# RPi-WS2812-HAT_v10.net
KiCad netlist of a schematic drawn in EAGLE
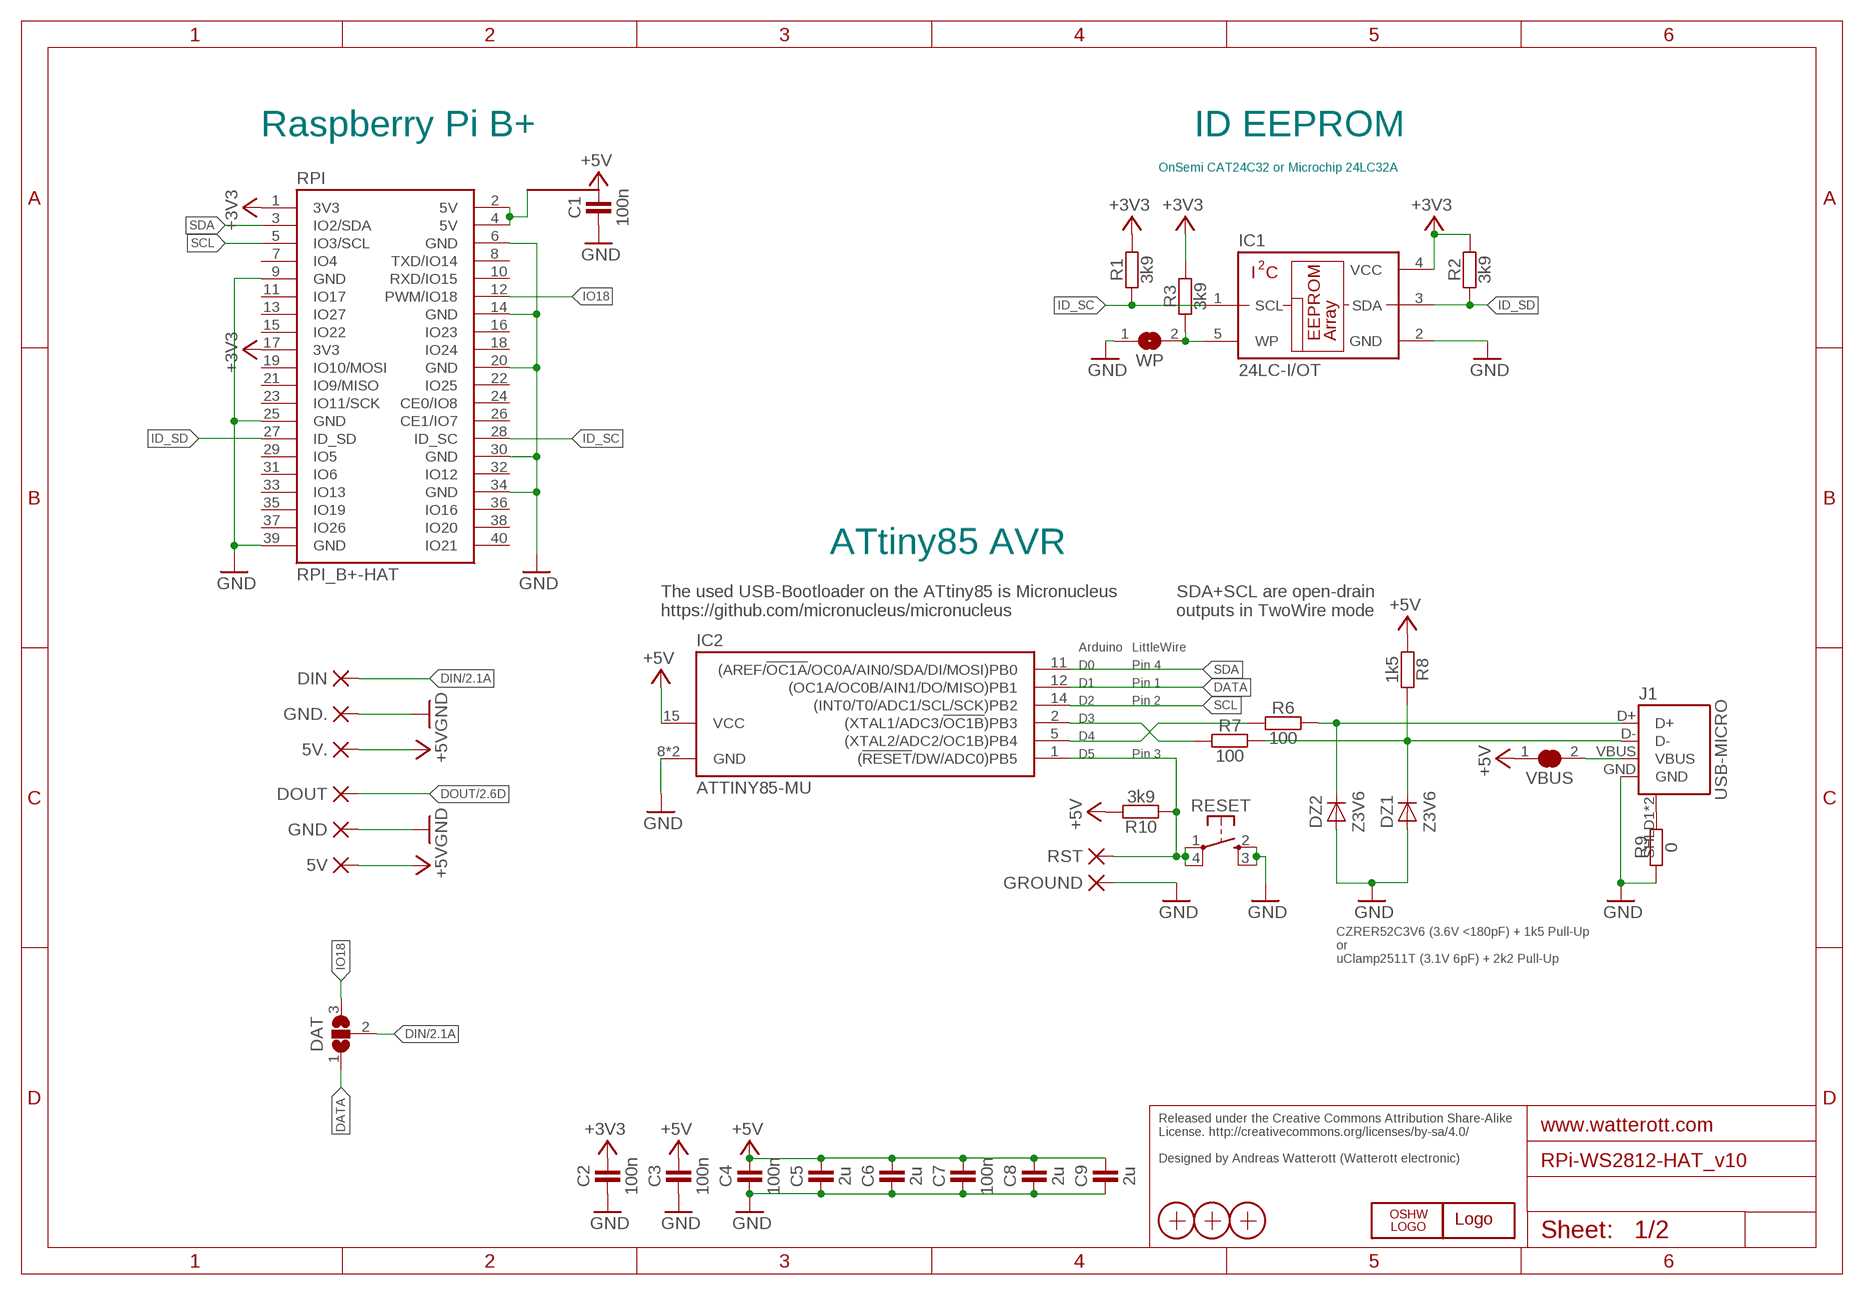
[diagram p0: schematic, sheet 1]
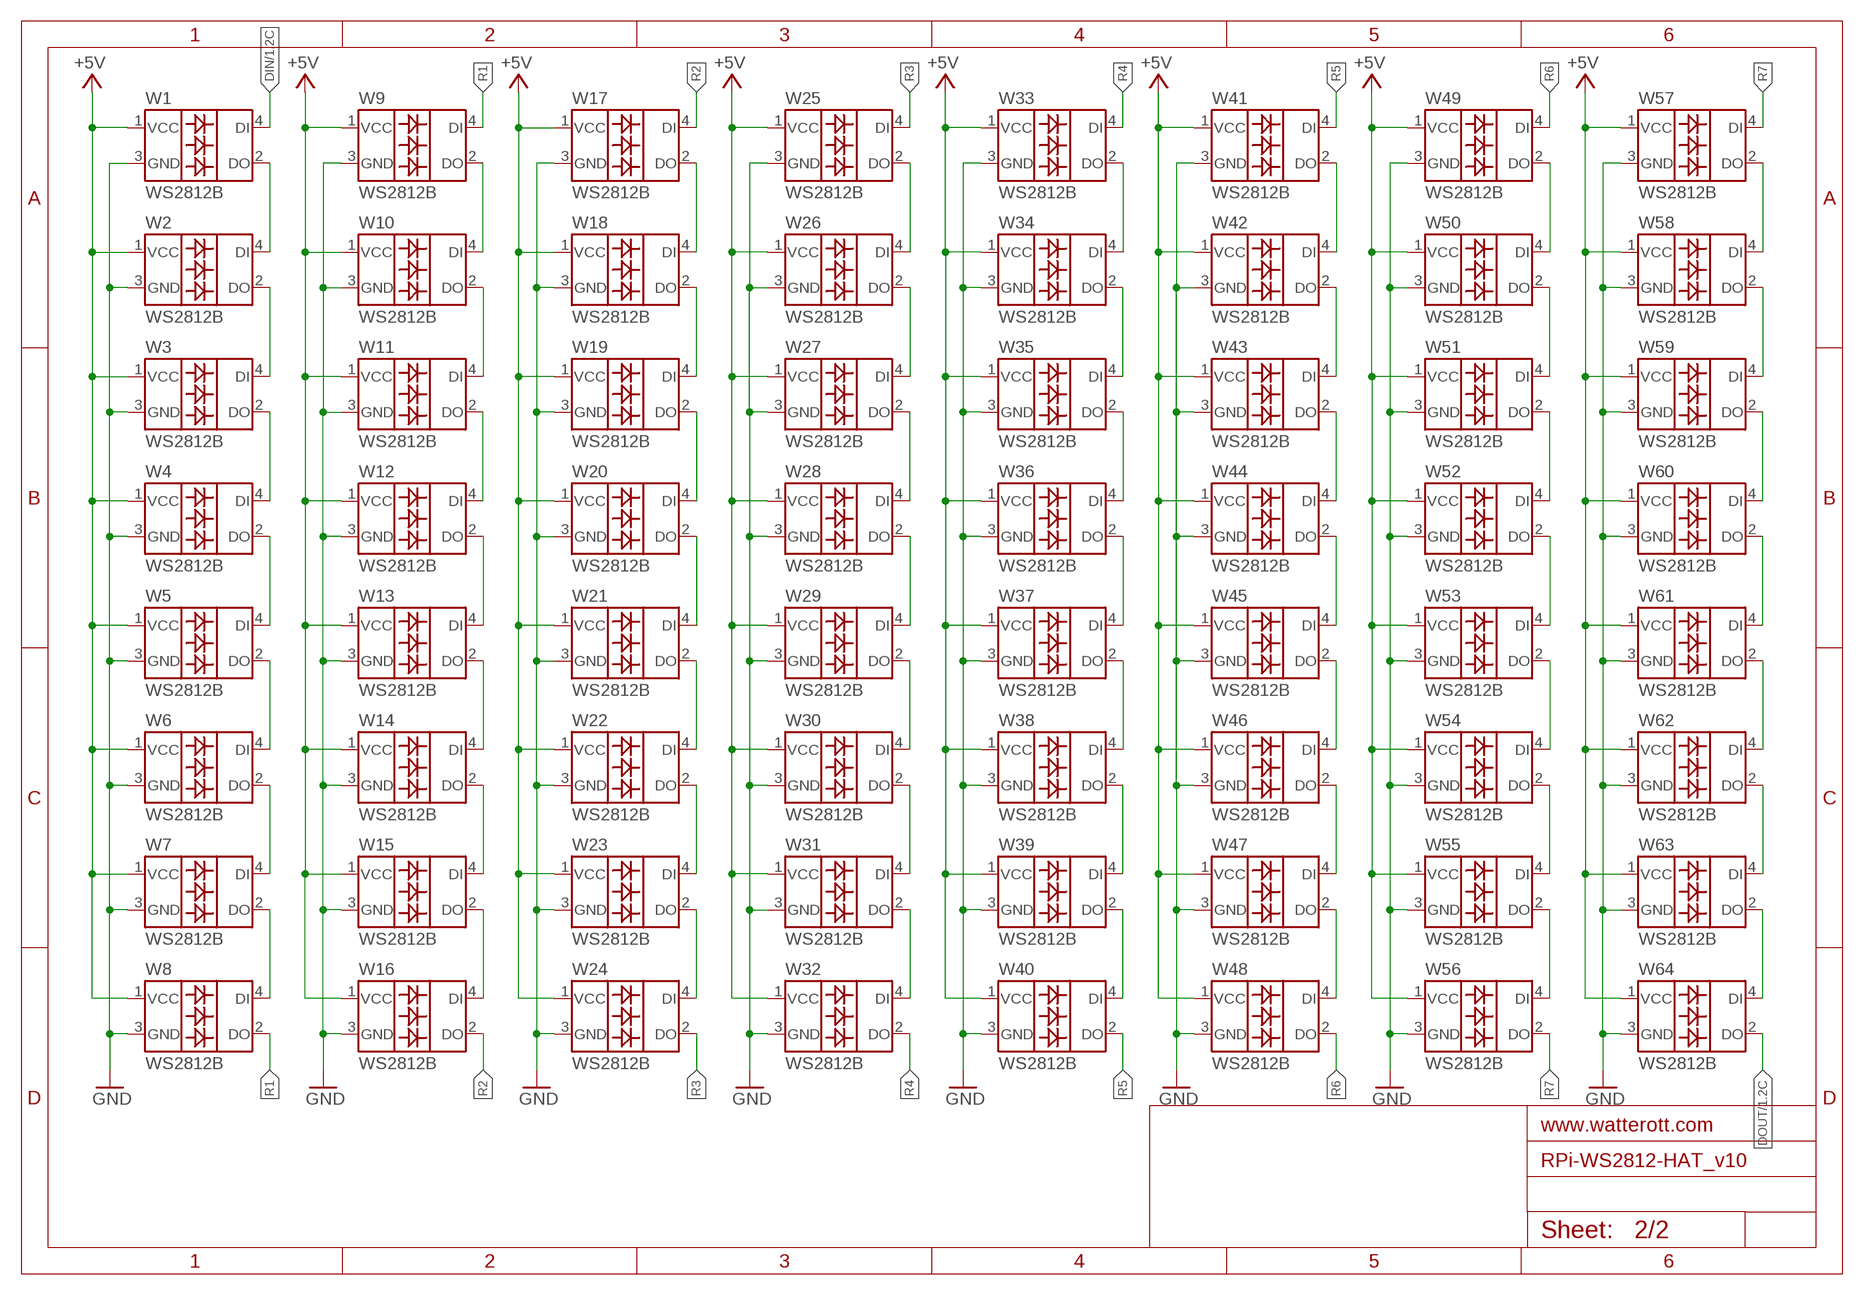
[diagram p1: schematic, sheet 2]

(export (version "E")
  (design (tool "Eeschema 10.0.6"))
  (components
    (comp (ref "5V")
      (value "PAD-1.27X2.54_NC")
      (footprint "eagle-import:PAD-1.27X2.54_NC")
      (libsource (lib "eagle-import") (part "PAD-1.27X2.54_NC"))
    )
    (comp (ref "5V.")
      (value "PAD-1.27X2.54_NC")
      (footprint "eagle-import:PAD-1.27X2.54_NC")
      (libsource (lib "eagle-import") (part "PAD-1.27X2.54_NC"))
    )
    (comp (ref "C1")
      (value "100n")
      (footprint "eagle-import:C0402")
      (libsource (lib "eagle-import") (part "CAPACITOR-0402"))
    )
    (comp (ref "C2")
      (value "100n")
      (footprint "eagle-import:C0402")
      (libsource (lib "eagle-import") (part "CAPACITOR-0402"))
    )
    (comp (ref "C3")
      (value "100n")
      (footprint "eagle-import:C0402")
      (libsource (lib "eagle-import") (part "CAPACITOR-0402"))
    )
    (comp (ref "C4")
      (value "100n")
      (footprint "eagle-import:C0402")
      (libsource (lib "eagle-import") (part "CAPACITOR-0402"))
    )
    (comp (ref "C5")
      (value "2u")
      (footprint "eagle-import:C0402")
      (libsource (lib "eagle-import") (part "CAPACITOR-0402"))
    )
    (comp (ref "C6")
      (value "2u")
      (footprint "eagle-import:C0402")
      (libsource (lib "eagle-import") (part "CAPACITOR-0402"))
    )
    (comp (ref "C7")
      (value "100n")
      (footprint "eagle-import:C0402")
      (libsource (lib "eagle-import") (part "CAPACITOR-0402"))
    )
    (comp (ref "C8")
      (value "2u")
      (footprint "eagle-import:C0402")
      (libsource (lib "eagle-import") (part "CAPACITOR-0402"))
    )
    (comp (ref "C9")
      (value "2u")
      (footprint "eagle-import:C0402")
      (libsource (lib "eagle-import") (part "CAPACITOR-0402"))
    )
    (comp (ref "DAT")
      (value "JUMPER3-0603")
      (footprint "eagle-import:JUMPER3-0603")
      (libsource (lib "eagle-import") (part "JUMPER3-0603"))
    )
    (comp (ref "DIN")
      (value "PAD-1.27X2.54_NC")
      (footprint "eagle-import:PAD-1.27X2.54_NC")
      (libsource (lib "eagle-import") (part "PAD-1.27X2.54_NC"))
    )
    (comp (ref "DOUT")
      (value "PAD-1.27X2.54_NC")
      (footprint "eagle-import:PAD-1.27X2.54_NC")
      (libsource (lib "eagle-import") (part "PAD-1.27X2.54_NC"))
    )
    (comp (ref "DZ1")
      (value "Z3V6")
      (footprint "eagle-import:SOD882")
      (libsource (lib "eagle-import") (part "DIODE-SOD882"))
    )
    (comp (ref "DZ2")
      (value "Z3V6")
      (footprint "eagle-import:SOD882")
      (libsource (lib "eagle-import") (part "DIODE-SOD882"))
    )
    (comp (ref "GND")
      (value "PAD-1.27X2.54_NC")
      (footprint "eagle-import:PAD-1.27X2.54_NC")
      (libsource (lib "eagle-import") (part "PAD-1.27X2.54_NC"))
    )
    (comp (ref "GND.")
      (value "PAD-1.27X2.54_NC")
      (footprint "eagle-import:PAD-1.27X2.54_NC")
      (libsource (lib "eagle-import") (part "PAD-1.27X2.54_NC"))
    )
    (comp (ref "GROUND")
      (value "PAD-1.27X1.27_NC")
      (footprint "eagle-import:PAD-1.27X1.27_NC")
      (libsource (lib "eagle-import") (part "PAD-1.27X1.27_NC"))
    )
    (comp (ref "IC1")
      (value "24LC-I/OT")
      (footprint "eagle-import:SOT23-5")
      (libsource (lib "eagle-import") (part "24LC-I/OT"))
    )
    (comp (ref "IC2")
      (value "ATTINY85-MU")
      (footprint "eagle-import:QFN20-PAD")
      (libsource (lib "eagle-import") (part "ATTINY85-MU"))
    )
    (comp (ref "J1")
      (value "USB-MICRO")
      (footprint "eagle-import:USB-MICRO-10103594")
      (libsource (lib "eagle-import") (part "USB-MICRO"))
    )
    (comp (ref "LOGO1")
      (value "LOGO-S_PLACE_S")
      (footprint "eagle-import:SPARK_TPLACE_S")
      (libsource (lib "eagle-import") (part "LOGO-S_PLACE_S"))
    )
    (comp (ref "LOGO2")
      (value "OSHW_LOGOX0070")
      (footprint "eagle-import:OSHW_6X70")
      (libsource (lib "eagle-import") (part "OSHW_LOGOX0070"))
    )
    (comp (ref "R1")
      (value "3k9")
      (footprint "eagle-import:C0402")
      (libsource (lib "eagle-import") (part "RESISTOR-0402"))
    )
    (comp (ref "R2")
      (value "3k9")
      (footprint "eagle-import:C0402")
      (libsource (lib "eagle-import") (part "RESISTOR-0402"))
    )
    (comp (ref "R3")
      (value "3k9")
      (footprint "eagle-import:C0402")
      (libsource (lib "eagle-import") (part "RESISTOR-0402"))
    )
    (comp (ref "R6")
      (value "100")
      (footprint "eagle-import:C0402")
      (libsource (lib "eagle-import") (part "RESISTOR-0402"))
    )
    (comp (ref "R7")
      (value "100")
      (footprint "eagle-import:C0402")
      (libsource (lib "eagle-import") (part "RESISTOR-0402"))
    )
    (comp (ref "R8")
      (value "1k5")
      (footprint "eagle-import:C0402")
      (libsource (lib "eagle-import") (part "RESISTOR-0402"))
    )
    (comp (ref "R9")
      (value "0")
      (footprint "eagle-import:C0402")
      (libsource (lib "eagle-import") (part "RESISTOR-0402"))
    )
    (comp (ref "R10")
      (value "3k9")
      (footprint "eagle-import:C0402")
      (libsource (lib "eagle-import") (part "RESISTOR-0402"))
    )
    (comp (ref "RESET")
      (value "SW-TACTILE-TL3315")
      (footprint "eagle-import:SW_TL3315N")
      (libsource (lib "eagle-import") (part "SW-TACTILE-TL3315"))
    )
    (comp (ref "RPI")
      (value "RPI_B+-HAT")
      (footprint "eagle-import:RPI-B+HAT")
      (libsource (lib "eagle-import") (part "RPI_B+-HAT"))
    )
    (comp (ref "RST")
      (value "PAD-1.27X1.27_NC")
      (footprint "eagle-import:PAD-1.27X1.27_NC")
      (libsource (lib "eagle-import") (part "PAD-1.27X1.27_NC"))
    )
    (comp (ref "VBUS")
      (value "JUMPER2-0603-NC")
      (footprint "eagle-import:JUMPER2-0603_NC")
      (libsource (lib "eagle-import") (part "JUMPER2-0603-NC"))
    )
    (comp (ref "WP")
      (value "JUMPER2-0603-NC")
      (footprint "eagle-import:JUMPER2-0603_NC")
      (libsource (lib "eagle-import") (part "JUMPER2-0603-NC"))
    )
    (comp (ref "X1")
      (value "PASSER-07")
      (footprint "eagle-import:PASSER_07MM")
      (libsource (lib "eagle-import") (part "PASSER-07"))
    )
    (comp (ref "X2")
      (value "PASSER-07")
      (footprint "eagle-import:PASSER_07MM")
      (libsource (lib "eagle-import") (part "PASSER-07"))
    )
    (comp (ref "X3")
      (value "PASSER-07")
      (footprint "eagle-import:PASSER_07MM")
      (libsource (lib "eagle-import") (part "PASSER-07"))
    )
    (comp (ref "W1")
      (value "WS2812B")
      (footprint "eagle-import:WS2812B")
      (libsource (lib "eagle-import") (part "WS2812B"))
    )
    (comp (ref "W2")
      (value "WS2812B")
      (footprint "eagle-import:WS2812B")
      (libsource (lib "eagle-import") (part "WS2812B"))
    )
    (comp (ref "W3")
      (value "WS2812B")
      (footprint "eagle-import:WS2812B")
      (libsource (lib "eagle-import") (part "WS2812B"))
    )
    (comp (ref "W4")
      (value "WS2812B")
      (footprint "eagle-import:WS2812B")
      (libsource (lib "eagle-import") (part "WS2812B"))
    )
    (comp (ref "W5")
      (value "WS2812B")
      (footprint "eagle-import:WS2812B")
      (libsource (lib "eagle-import") (part "WS2812B"))
    )
    (comp (ref "W6")
      (value "WS2812B")
      (footprint "eagle-import:WS2812B")
      (libsource (lib "eagle-import") (part "WS2812B"))
    )
    (comp (ref "W7")
      (value "WS2812B")
      (footprint "eagle-import:WS2812B")
      (libsource (lib "eagle-import") (part "WS2812B"))
    )
    (comp (ref "W8")
      (value "WS2812B")
      (footprint "eagle-import:WS2812B")
      (libsource (lib "eagle-import") (part "WS2812B"))
    )
    (comp (ref "W9")
      (value "WS2812B")
      (footprint "eagle-import:WS2812B")
      (libsource (lib "eagle-import") (part "WS2812B"))
    )
    (comp (ref "W10")
      (value "WS2812B")
      (footprint "eagle-import:WS2812B")
      (libsource (lib "eagle-import") (part "WS2812B"))
    )
    (comp (ref "W11")
      (value "WS2812B")
      (footprint "eagle-import:WS2812B")
      (libsource (lib "eagle-import") (part "WS2812B"))
    )
    (comp (ref "W12")
      (value "WS2812B")
      (footprint "eagle-import:WS2812B")
      (libsource (lib "eagle-import") (part "WS2812B"))
    )
    (comp (ref "W13")
      (value "WS2812B")
      (footprint "eagle-import:WS2812B")
      (libsource (lib "eagle-import") (part "WS2812B"))
    )
    (comp (ref "W14")
      (value "WS2812B")
      (footprint "eagle-import:WS2812B")
      (libsource (lib "eagle-import") (part "WS2812B"))
    )
    (comp (ref "W15")
      (value "WS2812B")
      (footprint "eagle-import:WS2812B")
      (libsource (lib "eagle-import") (part "WS2812B"))
    )
    (comp (ref "W16")
      (value "WS2812B")
      (footprint "eagle-import:WS2812B")
      (libsource (lib "eagle-import") (part "WS2812B"))
    )
    (comp (ref "W17")
      (value "WS2812B")
      (footprint "eagle-import:WS2812B")
      (libsource (lib "eagle-import") (part "WS2812B"))
    )
    (comp (ref "W18")
      (value "WS2812B")
      (footprint "eagle-import:WS2812B")
      (libsource (lib "eagle-import") (part "WS2812B"))
    )
    (comp (ref "W19")
      (value "WS2812B")
      (footprint "eagle-import:WS2812B")
      (libsource (lib "eagle-import") (part "WS2812B"))
    )
    (comp (ref "W20")
      (value "WS2812B")
      (footprint "eagle-import:WS2812B")
      (libsource (lib "eagle-import") (part "WS2812B"))
    )
    (comp (ref "W21")
      (value "WS2812B")
      (footprint "eagle-import:WS2812B")
      (libsource (lib "eagle-import") (part "WS2812B"))
    )
    (comp (ref "W22")
      (value "WS2812B")
      (footprint "eagle-import:WS2812B")
      (libsource (lib "eagle-import") (part "WS2812B"))
    )
    (comp (ref "W23")
      (value "WS2812B")
      (footprint "eagle-import:WS2812B")
      (libsource (lib "eagle-import") (part "WS2812B"))
    )
    (comp (ref "W24")
      (value "WS2812B")
      (footprint "eagle-import:WS2812B")
      (libsource (lib "eagle-import") (part "WS2812B"))
    )
    (comp (ref "W25")
      (value "WS2812B")
      (footprint "eagle-import:WS2812B")
      (libsource (lib "eagle-import") (part "WS2812B"))
    )
    (comp (ref "W26")
      (value "WS2812B")
      (footprint "eagle-import:WS2812B")
      (libsource (lib "eagle-import") (part "WS2812B"))
    )
    (comp (ref "W27")
      (value "WS2812B")
      (footprint "eagle-import:WS2812B")
      (libsource (lib "eagle-import") (part "WS2812B"))
    )
    (comp (ref "W28")
      (value "WS2812B")
      (footprint "eagle-import:WS2812B")
      (libsource (lib "eagle-import") (part "WS2812B"))
    )
    (comp (ref "W29")
      (value "WS2812B")
      (footprint "eagle-import:WS2812B")
      (libsource (lib "eagle-import") (part "WS2812B"))
    )
    (comp (ref "W30")
      (value "WS2812B")
      (footprint "eagle-import:WS2812B")
      (libsource (lib "eagle-import") (part "WS2812B"))
    )
    (comp (ref "W31")
      (value "WS2812B")
      (footprint "eagle-import:WS2812B")
      (libsource (lib "eagle-import") (part "WS2812B"))
    )
    (comp (ref "W32")
      (value "WS2812B")
      (footprint "eagle-import:WS2812B")
      (libsource (lib "eagle-import") (part "WS2812B"))
    )
    (comp (ref "W33")
      (value "WS2812B")
      (footprint "eagle-import:WS2812B")
      (libsource (lib "eagle-import") (part "WS2812B"))
    )
    (comp (ref "W34")
      (value "WS2812B")
      (footprint "eagle-import:WS2812B")
      (libsource (lib "eagle-import") (part "WS2812B"))
    )
    (comp (ref "W35")
      (value "WS2812B")
      (footprint "eagle-import:WS2812B")
      (libsource (lib "eagle-import") (part "WS2812B"))
    )
    (comp (ref "W36")
      (value "WS2812B")
      (footprint "eagle-import:WS2812B")
      (libsource (lib "eagle-import") (part "WS2812B"))
    )
    (comp (ref "W37")
      (value "WS2812B")
      (footprint "eagle-import:WS2812B")
      (libsource (lib "eagle-import") (part "WS2812B"))
    )
    (comp (ref "W38")
      (value "WS2812B")
      (footprint "eagle-import:WS2812B")
      (libsource (lib "eagle-import") (part "WS2812B"))
    )
    (comp (ref "W39")
      (value "WS2812B")
      (footprint "eagle-import:WS2812B")
      (libsource (lib "eagle-import") (part "WS2812B"))
    )
    (comp (ref "W40")
      (value "WS2812B")
      (footprint "eagle-import:WS2812B")
      (libsource (lib "eagle-import") (part "WS2812B"))
    )
    (comp (ref "W41")
      (value "WS2812B")
      (footprint "eagle-import:WS2812B")
      (libsource (lib "eagle-import") (part "WS2812B"))
    )
    (comp (ref "W42")
      (value "WS2812B")
      (footprint "eagle-import:WS2812B")
      (libsource (lib "eagle-import") (part "WS2812B"))
    )
    (comp (ref "W43")
      (value "WS2812B")
      (footprint "eagle-import:WS2812B")
      (libsource (lib "eagle-import") (part "WS2812B"))
    )
    (comp (ref "W44")
      (value "WS2812B")
      (footprint "eagle-import:WS2812B")
      (libsource (lib "eagle-import") (part "WS2812B"))
    )
    (comp (ref "W45")
      (value "WS2812B")
      (footprint "eagle-import:WS2812B")
      (libsource (lib "eagle-import") (part "WS2812B"))
    )
    (comp (ref "W46")
      (value "WS2812B")
      (footprint "eagle-import:WS2812B")
      (libsource (lib "eagle-import") (part "WS2812B"))
    )
    (comp (ref "W47")
      (value "WS2812B")
      (footprint "eagle-import:WS2812B")
      (libsource (lib "eagle-import") (part "WS2812B"))
    )
    (comp (ref "W48")
      (value "WS2812B")
      (footprint "eagle-import:WS2812B")
      (libsource (lib "eagle-import") (part "WS2812B"))
    )
    (comp (ref "W49")
      (value "WS2812B")
      (footprint "eagle-import:WS2812B")
      (libsource (lib "eagle-import") (part "WS2812B"))
    )
    (comp (ref "W50")
      (value "WS2812B")
      (footprint "eagle-import:WS2812B")
      (libsource (lib "eagle-import") (part "WS2812B"))
    )
    (comp (ref "W51")
      (value "WS2812B")
      (footprint "eagle-import:WS2812B")
      (libsource (lib "eagle-import") (part "WS2812B"))
    )
    (comp (ref "W52")
      (value "WS2812B")
      (footprint "eagle-import:WS2812B")
      (libsource (lib "eagle-import") (part "WS2812B"))
    )
    (comp (ref "W53")
      (value "WS2812B")
      (footprint "eagle-import:WS2812B")
      (libsource (lib "eagle-import") (part "WS2812B"))
    )
    (comp (ref "W54")
      (value "WS2812B")
      (footprint "eagle-import:WS2812B")
      (libsource (lib "eagle-import") (part "WS2812B"))
    )
    (comp (ref "W55")
      (value "WS2812B")
      (footprint "eagle-import:WS2812B")
      (libsource (lib "eagle-import") (part "WS2812B"))
    )
    (comp (ref "W56")
      (value "WS2812B")
      (footprint "eagle-import:WS2812B")
      (libsource (lib "eagle-import") (part "WS2812B"))
    )
    (comp (ref "W57")
      (value "WS2812B")
      (footprint "eagle-import:WS2812B")
      (libsource (lib "eagle-import") (part "WS2812B"))
    )
    (comp (ref "W58")
      (value "WS2812B")
      (footprint "eagle-import:WS2812B")
      (libsource (lib "eagle-import") (part "WS2812B"))
    )
    (comp (ref "W59")
      (value "WS2812B")
      (footprint "eagle-import:WS2812B")
      (libsource (lib "eagle-import") (part "WS2812B"))
    )
    (comp (ref "W60")
      (value "WS2812B")
      (footprint "eagle-import:WS2812B")
      (libsource (lib "eagle-import") (part "WS2812B"))
    )
    (comp (ref "W61")
      (value "WS2812B")
      (footprint "eagle-import:WS2812B")
      (libsource (lib "eagle-import") (part "WS2812B"))
    )
    (comp (ref "W62")
      (value "WS2812B")
      (footprint "eagle-import:WS2812B")
      (libsource (lib "eagle-import") (part "WS2812B"))
    )
    (comp (ref "W63")
      (value "WS2812B")
      (footprint "eagle-import:WS2812B")
      (libsource (lib "eagle-import") (part "WS2812B"))
    )
    (comp (ref "W64")
      (value "WS2812B")
      (footprint "eagle-import:WS2812B")
      (libsource (lib "eagle-import") (part "WS2812B"))
    )
  )
  (nets
    (net (code "1") (name "+3V3") (class "Default")
      (node (ref "C2") (pin "2") (pinfunction "2_2") (pintype "passive"))
      (node (ref "IC1") (pin "4") (pinfunction "VCC_4") (pintype "power_in"))
      (node (ref "R1") (pin "2") (pinfunction "2_2") (pintype "passive"))
      (node (ref "R2") (pin "2") (pinfunction "2_2") (pintype "passive"))
      (node (ref "R3") (pin "2") (pinfunction "2_2") (pintype "passive"))
      (node (ref "RPI") (pin "1") (pinfunction "3V3_1") (pintype "passive"))
      (node (ref "RPI") (pin "17") (pinfunction "3V3_17") (pintype "passive"))
    )
    (net (code "2") (name "+5V") (class "Default")
      (node (ref "5V") (pin "1") (pinfunction "P_1") (pintype "passive"))
      (node (ref "5V.") (pin "1") (pinfunction "P_1") (pintype "passive"))
      (node (ref "C1") (pin "2") (pinfunction "2_2") (pintype "passive"))
      (node (ref "C3") (pin "2") (pinfunction "2_2") (pintype "passive"))
      (node (ref "C4") (pin "2") (pinfunction "2_2") (pintype "passive"))
      (node (ref "C5") (pin "2") (pinfunction "2_2") (pintype "passive"))
      (node (ref "C6") (pin "2") (pinfunction "2_2") (pintype "passive"))
      (node (ref "C7") (pin "2") (pinfunction "2_2") (pintype "passive"))
      (node (ref "C8") (pin "2") (pinfunction "2_2") (pintype "passive"))
      (node (ref "C9") (pin "2") (pinfunction "2_2") (pintype "passive"))
      (node (ref "IC2") (pin "15") (pinfunction "VCC_15") (pintype "power_in"))
      (node (ref "R10") (pin "2") (pinfunction "2_2") (pintype "passive"))
      (node (ref "R8") (pin "1") (pinfunction "1_1") (pintype "passive"))
      (node (ref "VBUS") (pin "1") (pinfunction "1_1") (pintype "passive"))
      (node (ref "W1") (pin "1") (pinfunction "VCC_1") (pintype "power_in"))
      (node (ref "W10") (pin "1") (pinfunction "VCC_1") (pintype "power_in"))
      (node (ref "W11") (pin "1") (pinfunction "VCC_1") (pintype "power_in"))
      (node (ref "W12") (pin "1") (pinfunction "VCC_1") (pintype "power_in"))
      (node (ref "W13") (pin "1") (pinfunction "VCC_1") (pintype "power_in"))
      (node (ref "W14") (pin "1") (pinfunction "VCC_1") (pintype "power_in"))
      (node (ref "W15") (pin "1") (pinfunction "VCC_1") (pintype "power_in"))
      (node (ref "W16") (pin "1") (pinfunction "VCC_1") (pintype "power_in"))
      (node (ref "W17") (pin "1") (pinfunction "VCC_1") (pintype "power_in"))
      (node (ref "W18") (pin "1") (pinfunction "VCC_1") (pintype "power_in"))
      (node (ref "W19") (pin "1") (pinfunction "VCC_1") (pintype "power_in"))
      (node (ref "W2") (pin "1") (pinfunction "VCC_1") (pintype "power_in"))
      (node (ref "W20") (pin "1") (pinfunction "VCC_1") (pintype "power_in"))
      (node (ref "W21") (pin "1") (pinfunction "VCC_1") (pintype "power_in"))
      (node (ref "W22") (pin "1") (pinfunction "VCC_1") (pintype "power_in"))
      (node (ref "W23") (pin "1") (pinfunction "VCC_1") (pintype "power_in"))
      (node (ref "W24") (pin "1") (pinfunction "VCC_1") (pintype "power_in"))
      (node (ref "W25") (pin "1") (pinfunction "VCC_1") (pintype "power_in"))
      (node (ref "W26") (pin "1") (pinfunction "VCC_1") (pintype "power_in"))
      (node (ref "W27") (pin "1") (pinfunction "VCC_1") (pintype "power_in"))
      (node (ref "W28") (pin "1") (pinfunction "VCC_1") (pintype "power_in"))
      (node (ref "W29") (pin "1") (pinfunction "VCC_1") (pintype "power_in"))
      (node (ref "W3") (pin "1") (pinfunction "VCC_1") (pintype "power_in"))
      (node (ref "W30") (pin "1") (pinfunction "VCC_1") (pintype "power_in"))
      (node (ref "W31") (pin "1") (pinfunction "VCC_1") (pintype "power_in"))
      (node (ref "W32") (pin "1") (pinfunction "VCC_1") (pintype "power_in"))
      (node (ref "W33") (pin "1") (pinfunction "VCC_1") (pintype "power_in"))
      (node (ref "W34") (pin "1") (pinfunction "VCC_1") (pintype "power_in"))
      (node (ref "W35") (pin "1") (pinfunction "VCC_1") (pintype "power_in"))
      (node (ref "W36") (pin "1") (pinfunction "VCC_1") (pintype "power_in"))
      (node (ref "W37") (pin "1") (pinfunction "VCC_1") (pintype "power_in"))
      (node (ref "W38") (pin "1") (pinfunction "VCC_1") (pintype "power_in"))
      (node (ref "W39") (pin "1") (pinfunction "VCC_1") (pintype "power_in"))
      (node (ref "W4") (pin "1") (pinfunction "VCC_1") (pintype "power_in"))
      (node (ref "W40") (pin "1") (pinfunction "VCC_1") (pintype "power_in"))
      (node (ref "W41") (pin "1") (pinfunction "VCC_1") (pintype "power_in"))
      (node (ref "W42") (pin "1") (pinfunction "VCC_1") (pintype "power_in"))
      (node (ref "W43") (pin "1") (pinfunction "VCC_1") (pintype "power_in"))
      (node (ref "W44") (pin "1") (pinfunction "VCC_1") (pintype "power_in"))
      (node (ref "W45") (pin "1") (pinfunction "VCC_1") (pintype "power_in"))
      (node (ref "W46") (pin "1") (pinfunction "VCC_1") (pintype "power_in"))
      (node (ref "W47") (pin "1") (pinfunction "VCC_1") (pintype "power_in"))
      (node (ref "W48") (pin "1") (pinfunction "VCC_1") (pintype "power_in"))
      (node (ref "W49") (pin "1") (pinfunction "VCC_1") (pintype "power_in"))
      (node (ref "W5") (pin "1") (pinfunction "VCC_1") (pintype "power_in"))
      (node (ref "W50") (pin "1") (pinfunction "VCC_1") (pintype "power_in"))
      (node (ref "W51") (pin "1") (pinfunction "VCC_1") (pintype "power_in"))
      (node (ref "W52") (pin "1") (pinfunction "VCC_1") (pintype "power_in"))
      (node (ref "W53") (pin "1") (pinfunction "VCC_1") (pintype "power_in"))
      (node (ref "W54") (pin "1") (pinfunction "VCC_1") (pintype "power_in"))
      (node (ref "W55") (pin "1") (pinfunction "VCC_1") (pintype "power_in"))
      (node (ref "W56") (pin "1") (pinfunction "VCC_1") (pintype "power_in"))
      (node (ref "W57") (pin "1") (pinfunction "VCC_1") (pintype "power_in"))
      (node (ref "W58") (pin "1") (pinfunction "VCC_1") (pintype "power_in"))
      (node (ref "W59") (pin "1") (pinfunction "VCC_1") (pintype "power_in"))
      (node (ref "W6") (pin "1") (pinfunction "VCC_1") (pintype "power_in"))
      (node (ref "W60") (pin "1") (pinfunction "VCC_1") (pintype "power_in"))
      (node (ref "W61") (pin "1") (pinfunction "VCC_1") (pintype "power_in"))
      (node (ref "W62") (pin "1") (pinfunction "VCC_1") (pintype "power_in"))
      (node (ref "W63") (pin "1") (pinfunction "VCC_1") (pintype "power_in"))
      (node (ref "W64") (pin "1") (pinfunction "VCC_1") (pintype "power_in"))
      (node (ref "W7") (pin "1") (pinfunction "VCC_1") (pintype "power_in"))
      (node (ref "W8") (pin "1") (pinfunction "VCC_1") (pintype "power_in"))
      (node (ref "W9") (pin "1") (pinfunction "VCC_1") (pintype "power_in"))
    )
    (net (code "3") (name "DATA") (class "Default")
      (node (ref "DAT") (pin "1") (pinfunction "1_1") (pintype "passive"))
      (node (ref "IC2") (pin "12") (pinfunction "(OC1A/OC0B/AIN1/DO/MISO)PB1_12") (pintype "bidirectional"))
    )
    (net (code "4") (name "DIN") (class "Default")
      (node (ref "DAT") (pin "2") (pinfunction "2_2") (pintype "passive"))
      (node (ref "DIN") (pin "1") (pinfunction "P_1") (pintype "passive"))
      (node (ref "W1") (pin "4") (pinfunction "DI_4") (pintype "bidirectional"))
    )
    (net (code "5") (name "DOUT") (class "Default")
      (node (ref "DOUT") (pin "1") (pinfunction "P_1") (pintype "passive"))
      (node (ref "W64") (pin "2") (pinfunction "DO_2") (pintype "bidirectional"))
    )
    (net (code "6") (name "GND") (class "Default")
      (node (ref "C1") (pin "1") (pinfunction "1_1") (pintype "passive"))
      (node (ref "C2") (pin "1") (pinfunction "1_1") (pintype "passive"))
      (node (ref "C3") (pin "1") (pinfunction "1_1") (pintype "passive"))
      (node (ref "C4") (pin "1") (pinfunction "1_1") (pintype "passive"))
      (node (ref "C5") (pin "1") (pinfunction "1_1") (pintype "passive"))
      (node (ref "C6") (pin "1") (pinfunction "1_1") (pintype "passive"))
      (node (ref "C7") (pin "1") (pinfunction "1_1") (pintype "passive"))
      (node (ref "C8") (pin "1") (pinfunction "1_1") (pintype "passive"))
      (node (ref "C9") (pin "1") (pinfunction "1_1") (pintype "passive"))
      (node (ref "DZ1") (pin "A") (pinfunction "A_A") (pintype "passive"))
      (node (ref "DZ2") (pin "A") (pinfunction "A_A") (pintype "passive"))
      (node (ref "GND") (pin "1") (pinfunction "P_1") (pintype "passive"))
      (node (ref "GND.") (pin "1") (pinfunction "P_1") (pintype "passive"))
      (node (ref "GROUND") (pin "1") (pinfunction "P_1") (pintype "passive"))
      (node (ref "IC1") (pin "2") (pinfunction "GND_2") (pintype "power_in"))
      (node (ref "IC2") (pin "8") (pinfunction "GND_8") (pintype "power_in"))
      (node (ref "IC2") (pin "TP") (pinfunction "GND_TP") (pintype "power_in"))
      (node (ref "J1") (pin "GND") (pinfunction "GND_GND") (pintype "power_in"))
      (node (ref "R9") (pin "1") (pinfunction "1_1") (pintype "passive"))
      (node (ref "RESET") (pin "2") (pinfunction "S1_2") (pintype "passive"))
      (node (ref "RESET") (pin "3") (pinfunction "S2_3") (pintype "passive"))
      (node (ref "RPI") (pin "14") (pinfunction "GND_14") (pintype "passive"))
      (node (ref "RPI") (pin "20") (pinfunction "GND_20") (pintype "passive"))
      (node (ref "RPI") (pin "25") (pinfunction "GND_25") (pintype "passive"))
      (node (ref "RPI") (pin "30") (pinfunction "GND_30") (pintype "bidirectional"))
      (node (ref "RPI") (pin "34") (pinfunction "GND_34") (pintype "bidirectional"))
      (node (ref "RPI") (pin "39") (pinfunction "GND_39") (pintype "bidirectional"))
      (node (ref "RPI") (pin "6") (pinfunction "GND_6") (pintype "passive"))
      (node (ref "RPI") (pin "9") (pinfunction "GND_9") (pintype "passive"))
      (node (ref "W1") (pin "3") (pinfunction "GND_3") (pintype "power_in"))
      (node (ref "W10") (pin "3") (pinfunction "GND_3") (pintype "power_in"))
      (node (ref "W11") (pin "3") (pinfunction "GND_3") (pintype "power_in"))
      (node (ref "W12") (pin "3") (pinfunction "GND_3") (pintype "power_in"))
      (node (ref "W13") (pin "3") (pinfunction "GND_3") (pintype "power_in"))
      (node (ref "W14") (pin "3") (pinfunction "GND_3") (pintype "power_in"))
      (node (ref "W15") (pin "3") (pinfunction "GND_3") (pintype "power_in"))
      (node (ref "W16") (pin "3") (pinfunction "GND_3") (pintype "power_in"))
      (node (ref "W17") (pin "3") (pinfunction "GND_3") (pintype "power_in"))
      (node (ref "W18") (pin "3") (pinfunction "GND_3") (pintype "power_in"))
      (node (ref "W19") (pin "3") (pinfunction "GND_3") (pintype "power_in"))
      (node (ref "W2") (pin "3") (pinfunction "GND_3") (pintype "power_in"))
      (node (ref "W20") (pin "3") (pinfunction "GND_3") (pintype "power_in"))
      (node (ref "W21") (pin "3") (pinfunction "GND_3") (pintype "power_in"))
      (node (ref "W22") (pin "3") (pinfunction "GND_3") (pintype "power_in"))
      (node (ref "W23") (pin "3") (pinfunction "GND_3") (pintype "power_in"))
      (node (ref "W24") (pin "3") (pinfunction "GND_3") (pintype "power_in"))
      (node (ref "W25") (pin "3") (pinfunction "GND_3") (pintype "power_in"))
      (node (ref "W26") (pin "3") (pinfunction "GND_3") (pintype "power_in"))
      (node (ref "W27") (pin "3") (pinfunction "GND_3") (pintype "power_in"))
      (node (ref "W28") (pin "3") (pinfunction "GND_3") (pintype "power_in"))
      (node (ref "W29") (pin "3") (pinfunction "GND_3") (pintype "power_in"))
      (node (ref "W3") (pin "3") (pinfunction "GND_3") (pintype "power_in"))
      (node (ref "W30") (pin "3") (pinfunction "GND_3") (pintype "power_in"))
      (node (ref "W31") (pin "3") (pinfunction "GND_3") (pintype "power_in"))
      (node (ref "W32") (pin "3") (pinfunction "GND_3") (pintype "power_in"))
      (node (ref "W33") (pin "3") (pinfunction "GND_3") (pintype "power_in"))
      (node (ref "W34") (pin "3") (pinfunction "GND_3") (pintype "power_in"))
      (node (ref "W35") (pin "3") (pinfunction "GND_3") (pintype "power_in"))
      (node (ref "W36") (pin "3") (pinfunction "GND_3") (pintype "power_in"))
      (node (ref "W37") (pin "3") (pinfunction "GND_3") (pintype "power_in"))
      (node (ref "W38") (pin "3") (pinfunction "GND_3") (pintype "power_in"))
      (node (ref "W39") (pin "3") (pinfunction "GND_3") (pintype "power_in"))
      (node (ref "W4") (pin "3") (pinfunction "GND_3") (pintype "power_in"))
      (node (ref "W40") (pin "3") (pinfunction "GND_3") (pintype "power_in"))
      (node (ref "W41") (pin "3") (pinfunction "GND_3") (pintype "power_in"))
      (node (ref "W42") (pin "3") (pinfunction "GND_3") (pintype "power_in"))
      (node (ref "W43") (pin "3") (pinfunction "GND_3") (pintype "power_in"))
      (node (ref "W44") (pin "3") (pinfunction "GND_3") (pintype "power_in"))
      (node (ref "W45") (pin "3") (pinfunction "GND_3") (pintype "power_in"))
      (node (ref "W46") (pin "3") (pinfunction "GND_3") (pintype "power_in"))
      (node (ref "W47") (pin "3") (pinfunction "GND_3") (pintype "power_in"))
      (node (ref "W48") (pin "3") (pinfunction "GND_3") (pintype "power_in"))
      (node (ref "W49") (pin "3") (pinfunction "GND_3") (pintype "power_in"))
      (node (ref "W5") (pin "3") (pinfunction "GND_3") (pintype "power_in"))
      (node (ref "W50") (pin "3") (pinfunction "GND_3") (pintype "power_in"))
      (node (ref "W51") (pin "3") (pinfunction "GND_3") (pintype "power_in"))
      (node (ref "W52") (pin "3") (pinfunction "GND_3") (pintype "power_in"))
      (node (ref "W53") (pin "3") (pinfunction "GND_3") (pintype "power_in"))
      (node (ref "W54") (pin "3") (pinfunction "GND_3") (pintype "power_in"))
      (node (ref "W55") (pin "3") (pinfunction "GND_3") (pintype "power_in"))
      (node (ref "W56") (pin "3") (pinfunction "GND_3") (pintype "power_in"))
      (node (ref "W57") (pin "3") (pinfunction "GND_3") (pintype "power_in"))
      (node (ref "W58") (pin "3") (pinfunction "GND_3") (pintype "power_in"))
      (node (ref "W59") (pin "3") (pinfunction "GND_3") (pintype "power_in"))
      (node (ref "W6") (pin "3") (pinfunction "GND_3") (pintype "power_in"))
      (node (ref "W60") (pin "3") (pinfunction "GND_3") (pintype "power_in"))
      (node (ref "W61") (pin "3") (pinfunction "GND_3") (pintype "power_in"))
      (node (ref "W62") (pin "3") (pinfunction "GND_3") (pintype "power_in"))
      (node (ref "W63") (pin "3") (pinfunction "GND_3") (pintype "power_in"))
      (node (ref "W64") (pin "3") (pinfunction "GND_3") (pintype "power_in"))
      (node (ref "W7") (pin "3") (pinfunction "GND_3") (pintype "power_in"))
      (node (ref "W8") (pin "3") (pinfunction "GND_3") (pintype "power_in"))
      (node (ref "W9") (pin "3") (pinfunction "GND_3") (pintype "power_in"))
      (node (ref "WP") (pin "1") (pinfunction "1_1") (pintype "passive"))
    )
    (net (code "7") (name "ID_SC") (class "Default")
      (node (ref "IC1") (pin "1") (pinfunction "SCL_1") (pintype "bidirectional"))
      (node (ref "R1") (pin "1") (pinfunction "1_1") (pintype "passive"))
      (node (ref "RPI") (pin "28") (pinfunction "ID_SC_28") (pintype "bidirectional"))
    )
    (net (code "8") (name "ID_SD") (class "Default")
      (node (ref "IC1") (pin "3") (pinfunction "SDA_3") (pintype "bidirectional"))
      (node (ref "R2") (pin "1") (pinfunction "1_1") (pintype "passive"))
      (node (ref "RPI") (pin "27") (pinfunction "ID_SD_27") (pintype "bidirectional"))
    )
    (net (code "9") (name "IO18") (class "Default")
      (node (ref "DAT") (pin "3") (pinfunction "3_3") (pintype "passive"))
      (node (ref "RPI") (pin "12") (pinfunction "PWM/IO18_12") (pintype "passive"))
    )
    (net (code "10") (name "Net-(DZ1-PadC)") (class "Default")
      (node (ref "DZ1") (pin "C") (pinfunction "C_C") (pintype "passive"))
      (node (ref "J1") (pin "D-") (pinfunction "D-_D-") (pintype "bidirectional"))
      (node (ref "R7") (pin "2") (pinfunction "2_2") (pintype "passive"))
      (node (ref "R8") (pin "2") (pinfunction "2_2") (pintype "passive"))
    )
    (net (code "11") (name "Net-(DZ2-PadC)") (class "Default")
      (node (ref "DZ2") (pin "C") (pinfunction "C_C") (pintype "passive"))
      (node (ref "J1") (pin "D+") (pinfunction "D+_D+") (pintype "bidirectional"))
      (node (ref "R6") (pin "2") (pinfunction "2_2") (pintype "passive"))
    )
    (net (code "12") (name "Net-(IC1-WP)") (class "Default")
      (node (ref "IC1") (pin "5") (pinfunction "WP_5") (pintype "bidirectional"))
      (node (ref "R3") (pin "1") (pinfunction "1_1") (pintype "passive"))
      (node (ref "WP") (pin "2") (pinfunction "2_2") (pintype "passive"))
    )
    (net (code "13") (name "Net-(IC2-(XTAL1{slash}ADC3{slash}~{OC1B})PB3)") (class "Default")
      (node (ref "IC2") (pin "2") (pinfunction "(XTAL1/ADC3/~{OC1B})PB3_2") (pintype "bidirectional"))
      (node (ref "R7") (pin "1") (pinfunction "1_1") (pintype "passive"))
    )
    (net (code "14") (name "Net-(IC2-(XTAL2{slash}ADC2{slash}OC1B)PB4)") (class "Default")
      (node (ref "IC2") (pin "5") (pinfunction "(XTAL2/ADC2/OC1B)PB4_5") (pintype "bidirectional"))
      (node (ref "R6") (pin "1") (pinfunction "1_1") (pintype "passive"))
    )
    (net (code "15") (name "Net-(IC2-(~{RESET}{slash}DW{slash}ADC0)PB5)") (class "Default")
      (node (ref "IC2") (pin "1") (pinfunction "(~{RESET}/DW/ADC0)PB5_1") (pintype "bidirectional"))
      (node (ref "R10") (pin "1") (pinfunction "1_1") (pintype "passive"))
      (node (ref "RESET") (pin "1") (pinfunction "P1_1") (pintype "passive"))
      (node (ref "RESET") (pin "4") (pinfunction "P2_4") (pintype "passive"))
      (node (ref "RST") (pin "1") (pinfunction "P_1") (pintype "passive"))
    )
    (net (code "16") (name "Net-(J1-PadVBUS)") (class "Default")
      (node (ref "J1") (pin "VBUS") (pinfunction "VBUS_VBUS") (pintype "power_in"))
      (node (ref "VBUS") (pin "2") (pinfunction "2_2") (pintype "passive"))
    )
    (net (code "17") (name "Net-(J1-SHIELD-PadSHLD1)") (class "Default")
      (node (ref "J1") (pin "SHLD1") (pinfunction "SHIELD_SHLD1") (pintype "passive"))
      (node (ref "J1") (pin "SHLD2") (pinfunction "SHIELD_SHLD2") (pintype "passive"))
      (node (ref "R9") (pin "2") (pinfunction "2_2") (pintype "passive"))
    )
    (net (code "18") (name "Net-(RPI-5V-Pad2)") (class "Default")
      (node (ref "RPI") (pin "2") (pinfunction "5V_2") (pintype "passive"))
      (node (ref "RPI") (pin "4") (pinfunction "5V_4") (pintype "passive"))
    )
    (net (code "19") (name "Net-(W1-DO)") (class "Default")
      (node (ref "W1") (pin "2") (pinfunction "DO_2") (pintype "bidirectional"))
      (node (ref "W2") (pin "4") (pinfunction "DI_4") (pintype "bidirectional"))
    )
    (net (code "20") (name "Net-(W2-DO)") (class "Default")
      (node (ref "W2") (pin "2") (pinfunction "DO_2") (pintype "bidirectional"))
      (node (ref "W3") (pin "4") (pinfunction "DI_4") (pintype "bidirectional"))
    )
    (net (code "21") (name "Net-(W3-DO)") (class "Default")
      (node (ref "W3") (pin "2") (pinfunction "DO_2") (pintype "bidirectional"))
      (node (ref "W4") (pin "4") (pinfunction "DI_4") (pintype "bidirectional"))
    )
    (net (code "22") (name "Net-(W4-DO)") (class "Default")
      (node (ref "W4") (pin "2") (pinfunction "DO_2") (pintype "bidirectional"))
      (node (ref "W5") (pin "4") (pinfunction "DI_4") (pintype "bidirectional"))
    )
    (net (code "23") (name "Net-(W5-DO)") (class "Default")
      (node (ref "W5") (pin "2") (pinfunction "DO_2") (pintype "bidirectional"))
      (node (ref "W6") (pin "4") (pinfunction "DI_4") (pintype "bidirectional"))
    )
    (net (code "24") (name "Net-(W6-DO)") (class "Default")
      (node (ref "W6") (pin "2") (pinfunction "DO_2") (pintype "bidirectional"))
      (node (ref "W7") (pin "4") (pinfunction "DI_4") (pintype "bidirectional"))
    )
    (net (code "25") (name "Net-(W7-DO)") (class "Default")
      (node (ref "W7") (pin "2") (pinfunction "DO_2") (pintype "bidirectional"))
      (node (ref "W8") (pin "4") (pinfunction "DI_4") (pintype "bidirectional"))
    )
    (net (code "26") (name "Net-(W10-DI)") (class "Default")
      (node (ref "W10") (pin "4") (pinfunction "DI_4") (pintype "bidirectional"))
      (node (ref "W9") (pin "2") (pinfunction "DO_2") (pintype "bidirectional"))
    )
    (net (code "27") (name "Net-(W10-DO)") (class "Default")
      (node (ref "W10") (pin "2") (pinfunction "DO_2") (pintype "bidirectional"))
      (node (ref "W11") (pin "4") (pinfunction "DI_4") (pintype "bidirectional"))
    )
    (net (code "28") (name "Net-(W11-DO)") (class "Default")
      (node (ref "W11") (pin "2") (pinfunction "DO_2") (pintype "bidirectional"))
      (node (ref "W12") (pin "4") (pinfunction "DI_4") (pintype "bidirectional"))
    )
    (net (code "29") (name "Net-(W12-DO)") (class "Default")
      (node (ref "W12") (pin "2") (pinfunction "DO_2") (pintype "bidirectional"))
      (node (ref "W13") (pin "4") (pinfunction "DI_4") (pintype "bidirectional"))
    )
    (net (code "30") (name "Net-(W13-DO)") (class "Default")
      (node (ref "W13") (pin "2") (pinfunction "DO_2") (pintype "bidirectional"))
      (node (ref "W14") (pin "4") (pinfunction "DI_4") (pintype "bidirectional"))
    )
    (net (code "31") (name "Net-(W14-DO)") (class "Default")
      (node (ref "W14") (pin "2") (pinfunction "DO_2") (pintype "bidirectional"))
      (node (ref "W15") (pin "4") (pinfunction "DI_4") (pintype "bidirectional"))
    )
    (net (code "32") (name "Net-(W15-DO)") (class "Default")
      (node (ref "W15") (pin "2") (pinfunction "DO_2") (pintype "bidirectional"))
      (node (ref "W16") (pin "4") (pinfunction "DI_4") (pintype "bidirectional"))
    )
    (net (code "33") (name "Net-(W17-DO)") (class "Default")
      (node (ref "W17") (pin "2") (pinfunction "DO_2") (pintype "bidirectional"))
      (node (ref "W18") (pin "4") (pinfunction "DI_4") (pintype "bidirectional"))
    )
    (net (code "34") (name "Net-(W18-DO)") (class "Default")
      (node (ref "W18") (pin "2") (pinfunction "DO_2") (pintype "bidirectional"))
      (node (ref "W19") (pin "4") (pinfunction "DI_4") (pintype "bidirectional"))
    )
    (net (code "35") (name "Net-(W19-DO)") (class "Default")
      (node (ref "W19") (pin "2") (pinfunction "DO_2") (pintype "bidirectional"))
      (node (ref "W20") (pin "4") (pinfunction "DI_4") (pintype "bidirectional"))
    )
    (net (code "36") (name "Net-(W20-DO)") (class "Default")
      (node (ref "W20") (pin "2") (pinfunction "DO_2") (pintype "bidirectional"))
      (node (ref "W21") (pin "4") (pinfunction "DI_4") (pintype "bidirectional"))
    )
    (net (code "37") (name "Net-(W21-DO)") (class "Default")
      (node (ref "W21") (pin "2") (pinfunction "DO_2") (pintype "bidirectional"))
      (node (ref "W22") (pin "4") (pinfunction "DI_4") (pintype "bidirectional"))
    )
    (net (code "38") (name "Net-(W22-DO)") (class "Default")
      (node (ref "W22") (pin "2") (pinfunction "DO_2") (pintype "bidirectional"))
      (node (ref "W23") (pin "4") (pinfunction "DI_4") (pintype "bidirectional"))
    )
    (net (code "39") (name "Net-(W23-DO)") (class "Default")
      (node (ref "W23") (pin "2") (pinfunction "DO_2") (pintype "bidirectional"))
      (node (ref "W24") (pin "4") (pinfunction "DI_4") (pintype "bidirectional"))
    )
    (net (code "40") (name "Net-(W25-DO)") (class "Default")
      (node (ref "W25") (pin "2") (pinfunction "DO_2") (pintype "bidirectional"))
      (node (ref "W26") (pin "4") (pinfunction "DI_4") (pintype "bidirectional"))
    )
    (net (code "41") (name "Net-(W26-DO)") (class "Default")
      (node (ref "W26") (pin "2") (pinfunction "DO_2") (pintype "bidirectional"))
      (node (ref "W27") (pin "4") (pinfunction "DI_4") (pintype "bidirectional"))
    )
    (net (code "42") (name "Net-(W27-DO)") (class "Default")
      (node (ref "W27") (pin "2") (pinfunction "DO_2") (pintype "bidirectional"))
      (node (ref "W28") (pin "4") (pinfunction "DI_4") (pintype "bidirectional"))
    )
    (net (code "43") (name "Net-(W28-DO)") (class "Default")
      (node (ref "W28") (pin "2") (pinfunction "DO_2") (pintype "bidirectional"))
      (node (ref "W29") (pin "4") (pinfunction "DI_4") (pintype "bidirectional"))
    )
    (net (code "44") (name "Net-(W29-DO)") (class "Default")
      (node (ref "W29") (pin "2") (pinfunction "DO_2") (pintype "bidirectional"))
      (node (ref "W30") (pin "4") (pinfunction "DI_4") (pintype "bidirectional"))
    )
    (net (code "45") (name "Net-(W30-DO)") (class "Default")
      (node (ref "W30") (pin "2") (pinfunction "DO_2") (pintype "bidirectional"))
      (node (ref "W31") (pin "4") (pinfunction "DI_4") (pintype "bidirectional"))
    )
    (net (code "46") (name "Net-(W31-DO)") (class "Default")
      (node (ref "W31") (pin "2") (pinfunction "DO_2") (pintype "bidirectional"))
      (node (ref "W32") (pin "4") (pinfunction "DI_4") (pintype "bidirectional"))
    )
    (net (code "47") (name "Net-(W33-DO)") (class "Default")
      (node (ref "W33") (pin "2") (pinfunction "DO_2") (pintype "bidirectional"))
      (node (ref "W34") (pin "4") (pinfunction "DI_4") (pintype "bidirectional"))
    )
    (net (code "48") (name "Net-(W34-DO)") (class "Default")
      (node (ref "W34") (pin "2") (pinfunction "DO_2") (pintype "bidirectional"))
      (node (ref "W35") (pin "4") (pinfunction "DI_4") (pintype "bidirectional"))
    )
    (net (code "49") (name "Net-(W35-DO)") (class "Default")
      (node (ref "W35") (pin "2") (pinfunction "DO_2") (pintype "bidirectional"))
      (node (ref "W36") (pin "4") (pinfunction "DI_4") (pintype "bidirectional"))
    )
    (net (code "50") (name "Net-(W36-DO)") (class "Default")
      (node (ref "W36") (pin "2") (pinfunction "DO_2") (pintype "bidirectional"))
      (node (ref "W37") (pin "4") (pinfunction "DI_4") (pintype "bidirectional"))
    )
    (net (code "51") (name "Net-(W37-DO)") (class "Default")
      (node (ref "W37") (pin "2") (pinfunction "DO_2") (pintype "bidirectional"))
      (node (ref "W38") (pin "4") (pinfunction "DI_4") (pintype "bidirectional"))
    )
    (net (code "52") (name "Net-(W38-DO)") (class "Default")
      (node (ref "W38") (pin "2") (pinfunction "DO_2") (pintype "bidirectional"))
      (node (ref "W39") (pin "4") (pinfunction "DI_4") (pintype "bidirectional"))
    )
    (net (code "53") (name "Net-(W39-DO)") (class "Default")
      (node (ref "W39") (pin "2") (pinfunction "DO_2") (pintype "bidirectional"))
      (node (ref "W40") (pin "4") (pinfunction "DI_4") (pintype "bidirectional"))
    )
    (net (code "54") (name "Net-(W41-DO)") (class "Default")
      (node (ref "W41") (pin "2") (pinfunction "DO_2") (pintype "bidirectional"))
      (node (ref "W42") (pin "4") (pinfunction "DI_4") (pintype "bidirectional"))
    )
    (net (code "55") (name "Net-(W42-DO)") (class "Default")
      (node (ref "W42") (pin "2") (pinfunction "DO_2") (pintype "bidirectional"))
      (node (ref "W43") (pin "4") (pinfunction "DI_4") (pintype "bidirectional"))
    )
    (net (code "56") (name "Net-(W43-DO)") (class "Default")
      (node (ref "W43") (pin "2") (pinfunction "DO_2") (pintype "bidirectional"))
      (node (ref "W44") (pin "4") (pinfunction "DI_4") (pintype "bidirectional"))
    )
    (net (code "57") (name "Net-(W44-DO)") (class "Default")
      (node (ref "W44") (pin "2") (pinfunction "DO_2") (pintype "bidirectional"))
      (node (ref "W45") (pin "4") (pinfunction "DI_4") (pintype "bidirectional"))
    )
    (net (code "58") (name "Net-(W45-DO)") (class "Default")
      (node (ref "W45") (pin "2") (pinfunction "DO_2") (pintype "bidirectional"))
      (node (ref "W46") (pin "4") (pinfunction "DI_4") (pintype "bidirectional"))
    )
    (net (code "59") (name "Net-(W46-DO)") (class "Default")
      (node (ref "W46") (pin "2") (pinfunction "DO_2") (pintype "bidirectional"))
      (node (ref "W47") (pin "4") (pinfunction "DI_4") (pintype "bidirectional"))
    )
    (net (code "60") (name "Net-(W47-DO)") (class "Default")
      (node (ref "W47") (pin "2") (pinfunction "DO_2") (pintype "bidirectional"))
      (node (ref "W48") (pin "4") (pinfunction "DI_4") (pintype "bidirectional"))
    )
    (net (code "61") (name "Net-(W49-DO)") (class "Default")
      (node (ref "W49") (pin "2") (pinfunction "DO_2") (pintype "bidirectional"))
      (node (ref "W50") (pin "4") (pinfunction "DI_4") (pintype "bidirectional"))
    )
    (net (code "62") (name "Net-(W50-DO)") (class "Default")
      (node (ref "W50") (pin "2") (pinfunction "DO_2") (pintype "bidirectional"))
      (node (ref "W51") (pin "4") (pinfunction "DI_4") (pintype "bidirectional"))
    )
    (net (code "63") (name "Net-(W51-DO)") (class "Default")
      (node (ref "W51") (pin "2") (pinfunction "DO_2") (pintype "bidirectional"))
      (node (ref "W52") (pin "4") (pinfunction "DI_4") (pintype "bidirectional"))
    )
    (net (code "64") (name "Net-(W52-DO)") (class "Default")
      (node (ref "W52") (pin "2") (pinfunction "DO_2") (pintype "bidirectional"))
      (node (ref "W53") (pin "4") (pinfunction "DI_4") (pintype "bidirectional"))
    )
    (net (code "65") (name "Net-(W53-DO)") (class "Default")
      (node (ref "W53") (pin "2") (pinfunction "DO_2") (pintype "bidirectional"))
      (node (ref "W54") (pin "4") (pinfunction "DI_4") (pintype "bidirectional"))
    )
    (net (code "66") (name "Net-(W54-DO)") (class "Default")
      (node (ref "W54") (pin "2") (pinfunction "DO_2") (pintype "bidirectional"))
      (node (ref "W55") (pin "4") (pinfunction "DI_4") (pintype "bidirectional"))
    )
    (net (code "67") (name "Net-(W55-DO)") (class "Default")
      (node (ref "W55") (pin "2") (pinfunction "DO_2") (pintype "bidirectional"))
      (node (ref "W56") (pin "4") (pinfunction "DI_4") (pintype "bidirectional"))
    )
    (net (code "68") (name "Net-(W57-DO)") (class "Default")
      (node (ref "W57") (pin "2") (pinfunction "DO_2") (pintype "bidirectional"))
      (node (ref "W58") (pin "4") (pinfunction "DI_4") (pintype "bidirectional"))
    )
    (net (code "69") (name "Net-(W58-DO)") (class "Default")
      (node (ref "W58") (pin "2") (pinfunction "DO_2") (pintype "bidirectional"))
      (node (ref "W59") (pin "4") (pinfunction "DI_4") (pintype "bidirectional"))
    )
    (net (code "70") (name "Net-(W59-DO)") (class "Default")
      (node (ref "W59") (pin "2") (pinfunction "DO_2") (pintype "bidirectional"))
      (node (ref "W60") (pin "4") (pinfunction "DI_4") (pintype "bidirectional"))
    )
    (net (code "71") (name "Net-(W60-DO)") (class "Default")
      (node (ref "W60") (pin "2") (pinfunction "DO_2") (pintype "bidirectional"))
      (node (ref "W61") (pin "4") (pinfunction "DI_4") (pintype "bidirectional"))
    )
    (net (code "72") (name "Net-(W61-DO)") (class "Default")
      (node (ref "W61") (pin "2") (pinfunction "DO_2") (pintype "bidirectional"))
      (node (ref "W62") (pin "4") (pinfunction "DI_4") (pintype "bidirectional"))
    )
    (net (code "73") (name "Net-(W62-DO)") (class "Default")
      (node (ref "W62") (pin "2") (pinfunction "DO_2") (pintype "bidirectional"))
      (node (ref "W63") (pin "4") (pinfunction "DI_4") (pintype "bidirectional"))
    )
    (net (code "74") (name "Net-(W63-DO)") (class "Default")
      (node (ref "W63") (pin "2") (pinfunction "DO_2") (pintype "bidirectional"))
      (node (ref "W64") (pin "4") (pinfunction "DI_4") (pintype "bidirectional"))
    )
    (net (code "75") (name "R1") (class "Default")
      (node (ref "W8") (pin "2") (pinfunction "DO_2") (pintype "bidirectional"))
      (node (ref "W9") (pin "4") (pinfunction "DI_4") (pintype "bidirectional"))
    )
    (net (code "76") (name "R2") (class "Default")
      (node (ref "W16") (pin "2") (pinfunction "DO_2") (pintype "bidirectional"))
      (node (ref "W17") (pin "4") (pinfunction "DI_4") (pintype "bidirectional"))
    )
    (net (code "77") (name "R3") (class "Default")
      (node (ref "W24") (pin "2") (pinfunction "DO_2") (pintype "bidirectional"))
      (node (ref "W25") (pin "4") (pinfunction "DI_4") (pintype "bidirectional"))
    )
    (net (code "78") (name "R4") (class "Default")
      (node (ref "W32") (pin "2") (pinfunction "DO_2") (pintype "bidirectional"))
      (node (ref "W33") (pin "4") (pinfunction "DI_4") (pintype "bidirectional"))
    )
    (net (code "79") (name "R5") (class "Default")
      (node (ref "W40") (pin "2") (pinfunction "DO_2") (pintype "bidirectional"))
      (node (ref "W41") (pin "4") (pinfunction "DI_4") (pintype "bidirectional"))
    )
    (net (code "80") (name "R6") (class "Default")
      (node (ref "W48") (pin "2") (pinfunction "DO_2") (pintype "bidirectional"))
      (node (ref "W49") (pin "4") (pinfunction "DI_4") (pintype "bidirectional"))
    )
    (net (code "81") (name "R7") (class "Default")
      (node (ref "W56") (pin "2") (pinfunction "DO_2") (pintype "bidirectional"))
      (node (ref "W57") (pin "4") (pinfunction "DI_4") (pintype "bidirectional"))
    )
    (net (code "82") (name "SCL") (class "Default")
      (node (ref "IC2") (pin "14") (pinfunction "(INT0/T0/ADC1/SCL/SCK)PB2_14") (pintype "bidirectional"))
      (node (ref "RPI") (pin "5") (pinfunction "IO3/SCL_5") (pintype "passive"))
    )
    (net (code "83") (name "SDA") (class "Default")
      (node (ref "IC2") (pin "11") (pinfunction "(AREF/~{OC1A}/OC0A/AIN0/SDA/DI/MOSI)PB0_11") (pintype "bidirectional"))
      (node (ref "RPI") (pin "3") (pinfunction "IO2/SDA_3") (pintype "passive"))
    )
    (net (code "84") (name "unconnected-(RPI-CE0{slash}IO8-Pad24)") (class "Default")
      (node (ref "RPI") (pin "24") (pinfunction "CE0/IO8_24") (pintype "passive"))
    )
    (net (code "85") (name "unconnected-(RPI-CE1{slash}IO7-Pad26)") (class "Default")
      (node (ref "RPI") (pin "26") (pinfunction "CE1/IO7_26") (pintype "passive"))
    )
    (net (code "86") (name "unconnected-(RPI-IO4-Pad7)") (class "Default")
      (node (ref "RPI") (pin "7") (pinfunction "IO4_7") (pintype "passive"))
    )
    (net (code "87") (name "unconnected-(RPI-IO5-Pad29)") (class "Default")
      (node (ref "RPI") (pin "29") (pinfunction "IO5_29") (pintype "bidirectional"))
    )
    (net (code "88") (name "unconnected-(RPI-IO6-Pad31)") (class "Default")
      (node (ref "RPI") (pin "31") (pinfunction "IO6_31") (pintype "bidirectional"))
    )
    (net (code "89") (name "unconnected-(RPI-IO9{slash}MISO-Pad21)") (class "Default")
      (node (ref "RPI") (pin "21") (pinfunction "IO9/MISO_21") (pintype "passive"))
    )
    (net (code "90") (name "unconnected-(RPI-IO10{slash}MOSI-Pad19)") (class "Default")
      (node (ref "RPI") (pin "19") (pinfunction "IO10/MOSI_19") (pintype "passive"))
    )
    (net (code "91") (name "unconnected-(RPI-IO11{slash}SCK-Pad23)") (class "Default")
      (node (ref "RPI") (pin "23") (pinfunction "IO11/SCK_23") (pintype "passive"))
    )
    (net (code "92") (name "unconnected-(RPI-IO12-Pad32)") (class "Default")
      (node (ref "RPI") (pin "32") (pinfunction "IO12_32") (pintype "bidirectional"))
    )
    (net (code "93") (name "unconnected-(RPI-IO13-Pad33)") (class "Default")
      (node (ref "RPI") (pin "33") (pinfunction "IO13_33") (pintype "bidirectional"))
    )
    (net (code "94") (name "unconnected-(RPI-IO16-Pad36)") (class "Default")
      (node (ref "RPI") (pin "36") (pinfunction "IO16_36") (pintype "bidirectional"))
    )
    (net (code "95") (name "unconnected-(RPI-IO17-Pad11)") (class "Default")
      (node (ref "RPI") (pin "11") (pinfunction "IO17_11") (pintype "passive"))
    )
    (net (code "96") (name "unconnected-(RPI-IO19-Pad35)") (class "Default")
      (node (ref "RPI") (pin "35") (pinfunction "IO19_35") (pintype "bidirectional"))
    )
    (net (code "97") (name "unconnected-(RPI-IO20-Pad38)") (class "Default")
      (node (ref "RPI") (pin "38") (pinfunction "IO20_38") (pintype "bidirectional"))
    )
    (net (code "98") (name "unconnected-(RPI-IO21-Pad40)") (class "Default")
      (node (ref "RPI") (pin "40") (pinfunction "IO21_40") (pintype "bidirectional"))
    )
    (net (code "99") (name "unconnected-(RPI-IO22-Pad15)") (class "Default")
      (node (ref "RPI") (pin "15") (pinfunction "IO22_15") (pintype "passive"))
    )
    (net (code "100") (name "unconnected-(RPI-IO23-Pad16)") (class "Default")
      (node (ref "RPI") (pin "16") (pinfunction "IO23_16") (pintype "passive"))
    )
    (net (code "101") (name "unconnected-(RPI-IO24-Pad18)") (class "Default")
      (node (ref "RPI") (pin "18") (pinfunction "IO24_18") (pintype "passive"))
    )
    (net (code "102") (name "unconnected-(RPI-IO25-Pad22)") (class "Default")
      (node (ref "RPI") (pin "22") (pinfunction "IO25_22") (pintype "passive"))
    )
    (net (code "103") (name "unconnected-(RPI-IO26-Pad37)") (class "Default")
      (node (ref "RPI") (pin "37") (pinfunction "IO26_37") (pintype "bidirectional"))
    )
    (net (code "104") (name "unconnected-(RPI-IO27-Pad13)") (class "Default")
      (node (ref "RPI") (pin "13") (pinfunction "IO27_13") (pintype "passive"))
    )
    (net (code "105") (name "unconnected-(RPI-RXD{slash}IO15-Pad10)") (class "Default")
      (node (ref "RPI") (pin "10") (pinfunction "RXD/IO15_10") (pintype "passive"))
    )
    (net (code "106") (name "unconnected-(RPI-TXD{slash}IO14-Pad8)") (class "Default")
      (node (ref "RPI") (pin "8") (pinfunction "TXD/IO14_8") (pintype "passive"))
    )
  )
)
